# doubler.net
KiCad netlist of a schematic drawn in Altium Designer
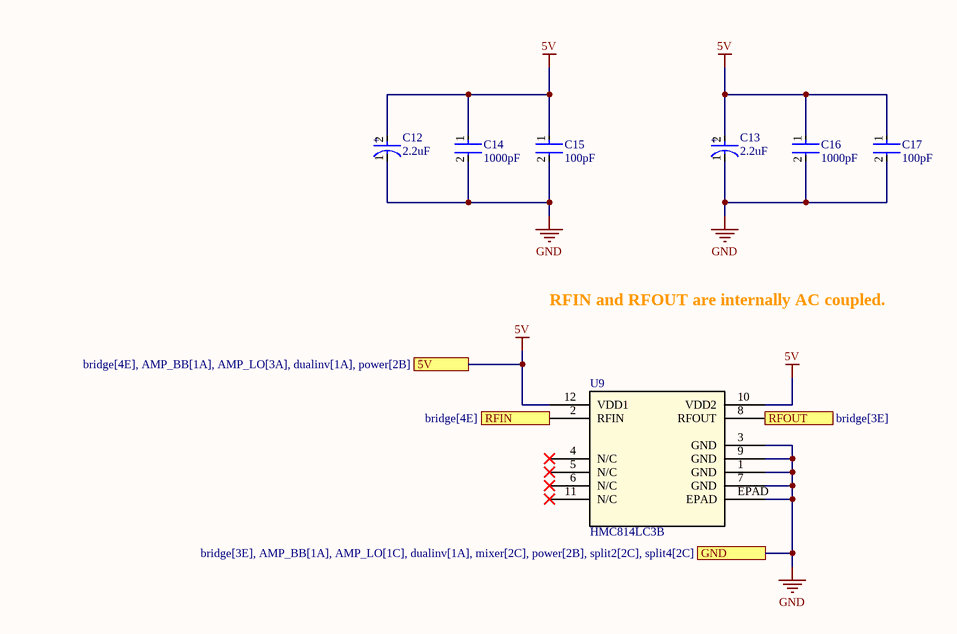
[diagram p0: doubler.SchDoc]

(export (version "E")
  (design (tool "Eeschema 10.0.6"))
  (components
    (comp (ref "C12")
      (value "2.2uF")
      (footprint "FP-TAJA-MFG")
      (description "2.2uF 16V  ±10% 6.5Ω 1206  SMD Tantalum Capacitor")
      (fields (field (name "TOLERANCE") "10%") (field (name "VOLTAGE") "16V"))
      (libsource (lib "FullLib") (part "CMP-04424-000432-1"))
    )
    (comp (ref "C13")
      (value "2.2uF")
      (footprint "FP-TAJA-MFG")
      (description "2.2uF 16V  ±10% 6.5Ω 1206  SMD Tantalum Capacitor")
      (fields (field (name "TOLERANCE") "10%") (field (name "VOLTAGE") "16V"))
      (libsource (lib "FullLib") (part "CMP-04424-000432-1"))
    )
    (comp (ref "C14")
      (value "1000pF")
      (footprint "FP-C0603C-CF-MFG")
      (description "CAP CER 1000PF 50V C0G/NP0 0603")
      (fields (field (name "MANUFACTURER") "Murata") (field (name "PART NUMBER") "GRM1885C1H102JA01D"))
      (libsource (lib "FullLib") (part "CMP-2006-03022-3"))
    )
    (comp (ref "C15")
      (value "100pF")
      (footprint "FP-CL05-MFG")
      (description "CAP CER 100PF 50V C0G/NP0 0402")
      (fields (field (name "MANUFACTURER") "Murata") (field (name "PART NUMBER") "GCM1555C1H101JA16D"))
      (libsource (lib "FullLib") (part "CMP-13271-000010-1"))
    )
    (comp (ref "C16")
      (value "1000pF")
      (footprint "FP-C0603C-CF-MFG")
      (description "CAP CER 1000PF 50V C0G/NP0 0603")
      (fields (field (name "MANUFACTURER") "Murata") (field (name "PART NUMBER") "GRM1885C1H102JA01D"))
      (libsource (lib "FullLib") (part "CMP-2006-03022-3"))
    )
    (comp (ref "C17")
      (value "100pF")
      (footprint "FP-CL05-MFG")
      (description "CAP CER 100PF 50V C0G/NP0 0402")
      (fields (field (name "MANUFACTURER") "Murata") (field (name "PART NUMBER") "GCM1555C1H101JA16D"))
      (libsource (lib "FullLib") (part "CMP-13271-000010-1"))
    )
    (comp (ref "U9")
      (value "HMC814LC3B")
      (footprint "HCP_12_1")
      (description "SMT GaAs MMIC x2 ACTIVE FREQUENCY\r\nMULTIPLIER, 13 - 24.6 GHz OUTPUT")
      (fields (field (name "MANUFACTURER") "Analog Devices"))
      (libsource (lib "FullyDigital") (part "HMC814LC3B"))
    )
  )
  (nets
    (net (code "1") (name "/RFIN") (class "Default")
      (node (ref "U9") (pin "2") (pinfunction "RFIN_2") (pintype "passive"))
    )
    (net (code "2") (name "/RFOUT") (class "Default")
      (node (ref "U9") (pin "8") (pinfunction "RFOUT_8") (pintype "passive"))
    )
    (net (code "3") (name "5V") (class "Default")
      (node (ref "C12") (pin "2") (pinfunction "A_2") (pintype "passive"))
      (node (ref "C13") (pin "2") (pinfunction "A_2") (pintype "passive"))
      (node (ref "C14") (pin "1") (pinfunction "1_1") (pintype "passive"))
      (node (ref "C15") (pin "1") (pinfunction "1_1") (pintype "passive"))
      (node (ref "C16") (pin "1") (pinfunction "1_1") (pintype "passive"))
      (node (ref "C17") (pin "1") (pinfunction "1_1") (pintype "passive"))
      (node (ref "U9") (pin "10") (pinfunction "VDD2_10") (pintype "passive"))
      (node (ref "U9") (pin "12") (pinfunction "VDD1_12") (pintype "passive"))
    )
    (net (code "4") (name "GND") (class "Default")
      (node (ref "C12") (pin "1") (pinfunction "C_1") (pintype "passive"))
      (node (ref "C13") (pin "1") (pinfunction "C_1") (pintype "passive"))
      (node (ref "C14") (pin "2") (pinfunction "2_2") (pintype "passive"))
      (node (ref "C15") (pin "2") (pinfunction "2_2") (pintype "passive"))
      (node (ref "C16") (pin "2") (pinfunction "2_2") (pintype "passive"))
      (node (ref "C17") (pin "2") (pinfunction "2_2") (pintype "passive"))
      (node (ref "U9") (pin "1") (pinfunction "GND_1") (pintype "passive"))
      (node (ref "U9") (pin "3") (pinfunction "GND_3") (pintype "passive"))
      (node (ref "U9") (pin "7") (pinfunction "GND_7") (pintype "passive"))
      (node (ref "U9") (pin "9") (pinfunction "GND_9") (pintype "passive"))
      (node (ref "U9") (pin "EPAD") (pinfunction "EPAD_EPAD") (pintype "passive"))
    )
    (net (code "5") (name "unconnected-(U9-N{slash}C-Pad4)") (class "Default")
      (node (ref "U9") (pin "4") (pinfunction "N/C_4") (pintype "passive+no_connect"))
    )
    (net (code "6") (name "unconnected-(U9-N{slash}C-Pad5)") (class "Default")
      (node (ref "U9") (pin "5") (pinfunction "N/C_5") (pintype "passive+no_connect"))
    )
    (net (code "7") (name "unconnected-(U9-N{slash}C-Pad6)") (class "Default")
      (node (ref "U9") (pin "6") (pinfunction "N/C_6") (pintype "passive+no_connect"))
    )
    (net (code "8") (name "unconnected-(U9-N{slash}C-Pad11)") (class "Default")
      (node (ref "U9") (pin "11") (pinfunction "N/C_11") (pintype "passive+no_connect"))
    )
  )
)
